# 32_smd.net
KiCad netlist of a schematic drawn in EAGLE
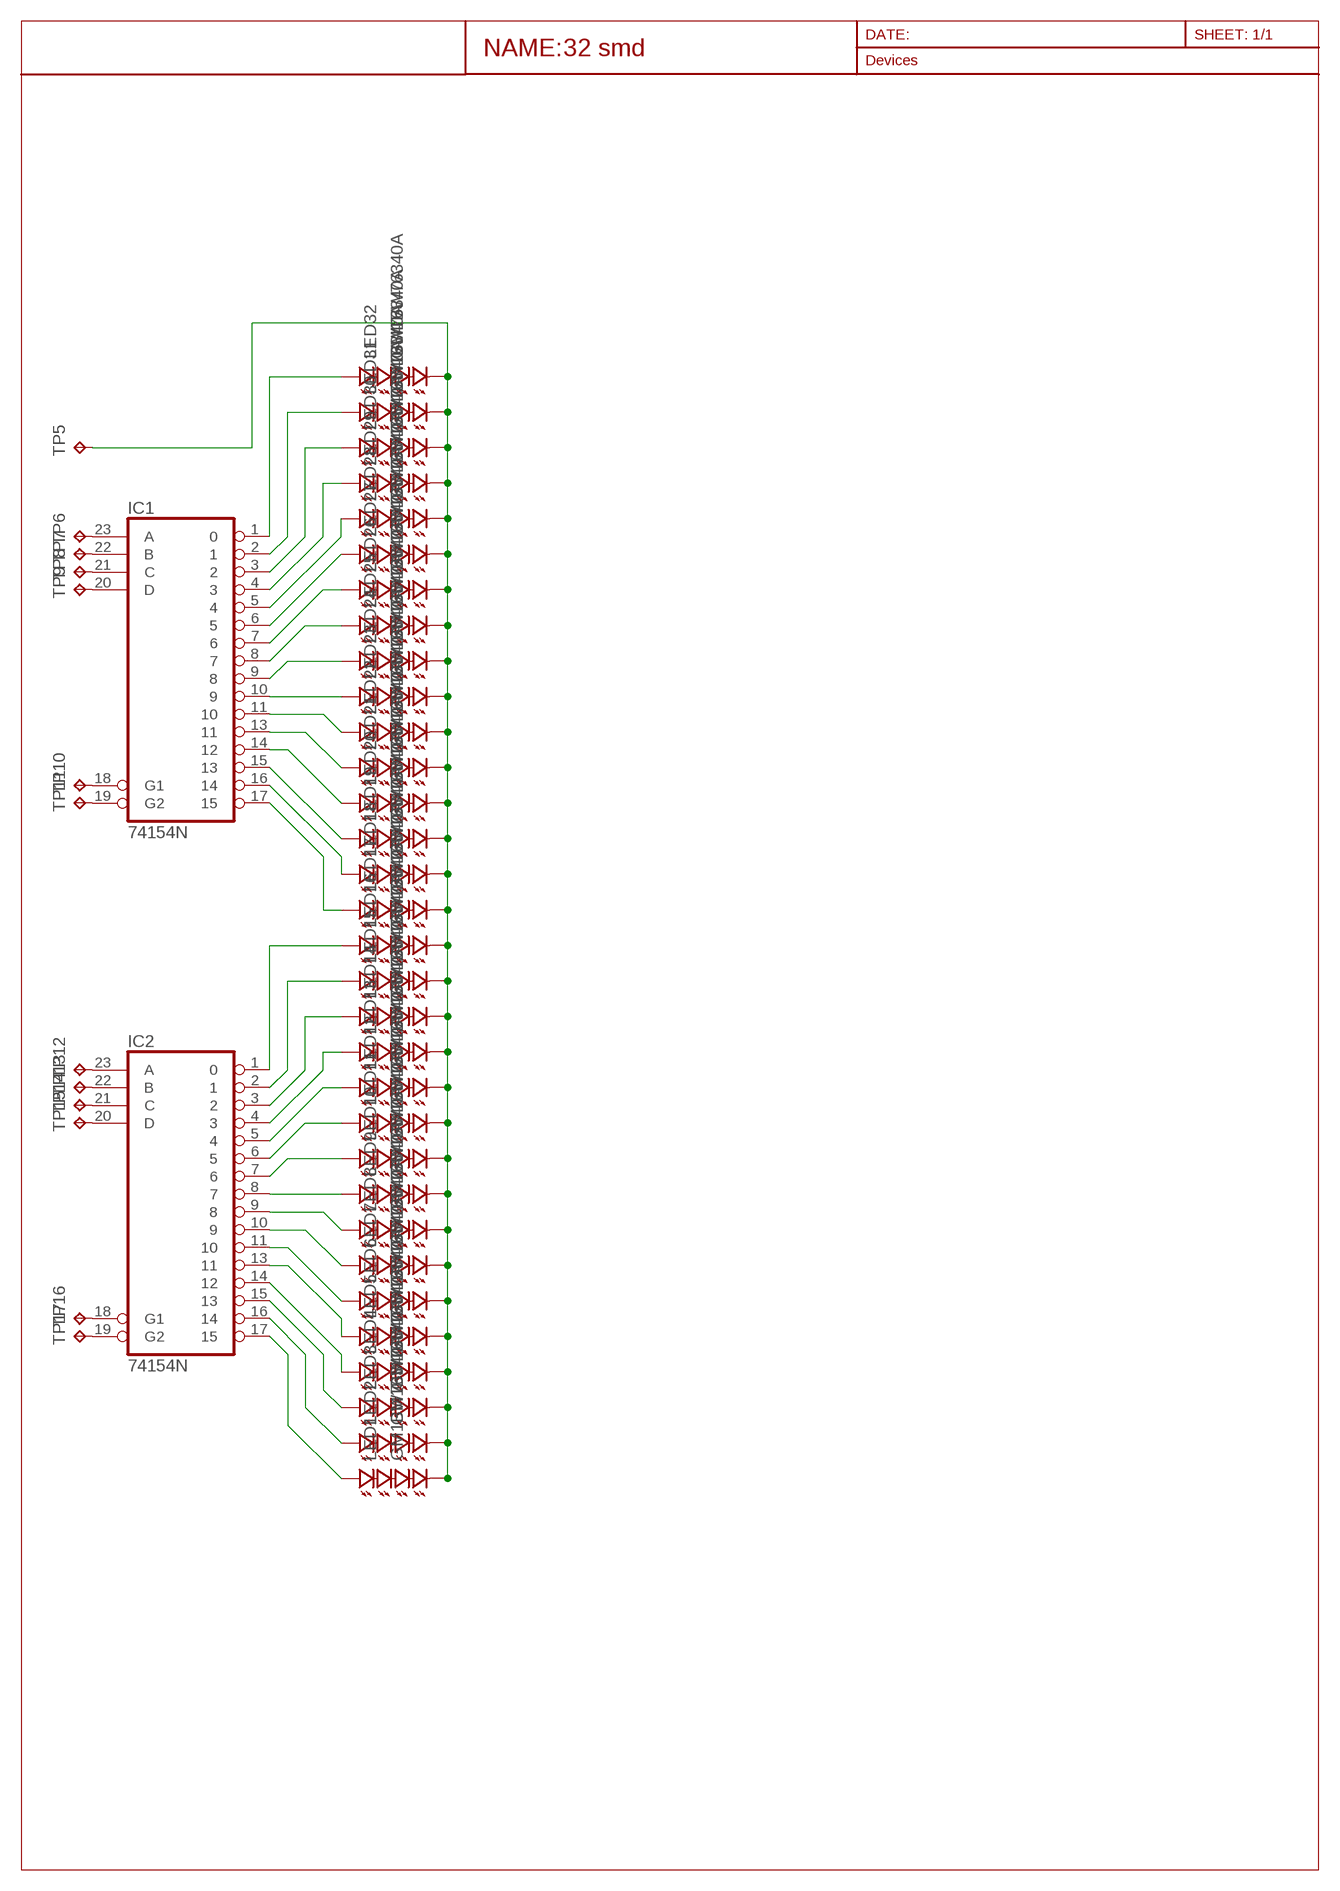
[diagram p0: schematic, sheet 1]

(export (version "E")
  (design (tool "Eeschema 10.0.6"))
  (components
    (comp (ref "IC1")
      (value "74154N")
      (footprint "eagle-import:DIL24-6")
      (libsource (lib "eagle-import") (part "74154N"))
    )
    (comp (ref "IC2")
      (value "74154N")
      (footprint "eagle-import:DIL24-6")
      (libsource (lib "eagle-import") (part "74154N"))
    )
    (comp (ref "LED1")
      (value "GM1BW76340A")
      (footprint "eagle-import:GM1BW78140A")
      (libsource (lib "eagle-import") (part "GM1BW76340A"))
    )
    (comp (ref "LED2")
      (value "GM1BW76340A")
      (footprint "eagle-import:GM1BW78140A")
      (libsource (lib "eagle-import") (part "GM1BW76340A"))
    )
    (comp (ref "LED3")
      (value "GM1BW76340A")
      (footprint "eagle-import:GM1BW78140A")
      (libsource (lib "eagle-import") (part "GM1BW76340A"))
    )
    (comp (ref "LED4")
      (value "GM1BW76340A")
      (footprint "eagle-import:GM1BW78140A")
      (libsource (lib "eagle-import") (part "GM1BW76340A"))
    )
    (comp (ref "LED5")
      (value "GM1BW76340A")
      (footprint "eagle-import:GM1BW78140A")
      (libsource (lib "eagle-import") (part "GM1BW76340A"))
    )
    (comp (ref "LED6")
      (value "GM1BW76340A")
      (footprint "eagle-import:GM1BW78140A")
      (libsource (lib "eagle-import") (part "GM1BW76340A"))
    )
    (comp (ref "LED7")
      (value "GM1BW76340A")
      (footprint "eagle-import:GM1BW78140A")
      (libsource (lib "eagle-import") (part "GM1BW76340A"))
    )
    (comp (ref "LED8")
      (value "GM1BW76340A")
      (footprint "eagle-import:GM1BW78140A")
      (libsource (lib "eagle-import") (part "GM1BW76340A"))
    )
    (comp (ref "LED9")
      (value "GM1BW76340A")
      (footprint "eagle-import:GM1BW78140A")
      (libsource (lib "eagle-import") (part "GM1BW76340A"))
    )
    (comp (ref "LED10")
      (value "GM1BW76340A")
      (footprint "eagle-import:GM1BW78140A")
      (libsource (lib "eagle-import") (part "GM1BW76340A"))
    )
    (comp (ref "LED11")
      (value "GM1BW76340A")
      (footprint "eagle-import:GM1BW78140A")
      (libsource (lib "eagle-import") (part "GM1BW76340A"))
    )
    (comp (ref "LED12")
      (value "GM1BW76340A")
      (footprint "eagle-import:GM1BW78140A")
      (libsource (lib "eagle-import") (part "GM1BW76340A"))
    )
    (comp (ref "LED13")
      (value "GM1BW76340A")
      (footprint "eagle-import:GM1BW78140A")
      (libsource (lib "eagle-import") (part "GM1BW76340A"))
    )
    (comp (ref "LED14")
      (value "GM1BW76340A")
      (footprint "eagle-import:GM1BW78140A")
      (libsource (lib "eagle-import") (part "GM1BW76340A"))
    )
    (comp (ref "LED15")
      (value "GM1BW76340A")
      (footprint "eagle-import:GM1BW78140A")
      (libsource (lib "eagle-import") (part "GM1BW76340A"))
    )
    (comp (ref "LED16")
      (value "GM1BW76340A")
      (footprint "eagle-import:GM1BW78140A")
      (libsource (lib "eagle-import") (part "GM1BW76340A"))
    )
    (comp (ref "LED17")
      (value "GM1BW76340A")
      (footprint "eagle-import:GM1BW78140A")
      (libsource (lib "eagle-import") (part "GM1BW76340A"))
    )
    (comp (ref "LED18")
      (value "GM1BW76340A")
      (footprint "eagle-import:GM1BW78140A")
      (libsource (lib "eagle-import") (part "GM1BW76340A"))
    )
    (comp (ref "LED19")
      (value "GM1BW76340A")
      (footprint "eagle-import:GM1BW78140A")
      (libsource (lib "eagle-import") (part "GM1BW76340A"))
    )
    (comp (ref "LED20")
      (value "GM1BW76340A")
      (footprint "eagle-import:GM1BW78140A")
      (libsource (lib "eagle-import") (part "GM1BW76340A"))
    )
    (comp (ref "LED21")
      (value "GM1BW76340A")
      (footprint "eagle-import:GM1BW78140A")
      (libsource (lib "eagle-import") (part "GM1BW76340A"))
    )
    (comp (ref "LED22")
      (value "GM1BW76340A")
      (footprint "eagle-import:GM1BW78140A")
      (libsource (lib "eagle-import") (part "GM1BW76340A"))
    )
    (comp (ref "LED23")
      (value "GM1BW76340A")
      (footprint "eagle-import:GM1BW78140A")
      (libsource (lib "eagle-import") (part "GM1BW76340A"))
    )
    (comp (ref "LED24")
      (value "GM1BW76340A")
      (footprint "eagle-import:GM1BW78140A")
      (libsource (lib "eagle-import") (part "GM1BW76340A"))
    )
    (comp (ref "LED25")
      (value "GM1BW76340A")
      (footprint "eagle-import:GM1BW78140A")
      (libsource (lib "eagle-import") (part "GM1BW76340A"))
    )
    (comp (ref "LED26")
      (value "GM1BW76340A")
      (footprint "eagle-import:GM1BW78140A")
      (libsource (lib "eagle-import") (part "GM1BW76340A"))
    )
    (comp (ref "LED27")
      (value "GM1BW76340A")
      (footprint "eagle-import:GM1BW78140A")
      (libsource (lib "eagle-import") (part "GM1BW76340A"))
    )
    (comp (ref "LED28")
      (value "GM1BW76340A")
      (footprint "eagle-import:GM1BW78140A")
      (libsource (lib "eagle-import") (part "GM1BW76340A"))
    )
    (comp (ref "LED29")
      (value "GM1BW76340A")
      (footprint "eagle-import:GM1BW78140A")
      (libsource (lib "eagle-import") (part "GM1BW76340A"))
    )
    (comp (ref "LED30")
      (value "GM1BW76340A")
      (footprint "eagle-import:GM1BW78140A")
      (libsource (lib "eagle-import") (part "GM1BW76340A"))
    )
    (comp (ref "LED31")
      (value "GM1BW76340A")
      (footprint "eagle-import:GM1BW78140A")
      (libsource (lib "eagle-import") (part "GM1BW76340A"))
    )
    (comp (ref "LED32")
      (value "GM1BW76340A")
      (footprint "eagle-import:GM1BW78140A")
      (libsource (lib "eagle-import") (part "GM1BW76340A"))
    )
    (comp (ref "TP5")
      (value "TPPAD1-17Y")
      (footprint "eagle-import:P1-17Y")
      (libsource (lib "eagle-import") (part "TPPAD1-17Y"))
    )
    (comp (ref "TP6")
      (value "TPPAD1-17Y")
      (footprint "eagle-import:P1-17Y")
      (libsource (lib "eagle-import") (part "TPPAD1-17Y"))
    )
    (comp (ref "TP7")
      (value "TPPAD1-17Y")
      (footprint "eagle-import:P1-17Y")
      (libsource (lib "eagle-import") (part "TPPAD1-17Y"))
    )
    (comp (ref "TP8")
      (value "TPPAD1-17Y")
      (footprint "eagle-import:P1-17Y")
      (libsource (lib "eagle-import") (part "TPPAD1-17Y"))
    )
    (comp (ref "TP9")
      (value "TPPAD1-17Y")
      (footprint "eagle-import:P1-17Y")
      (libsource (lib "eagle-import") (part "TPPAD1-17Y"))
    )
    (comp (ref "TP10")
      (value "TPPAD1-17Y")
      (footprint "eagle-import:P1-17Y")
      (libsource (lib "eagle-import") (part "TPPAD1-17Y"))
    )
    (comp (ref "TP11")
      (value "TPPAD1-17Y")
      (footprint "eagle-import:P1-17Y")
      (libsource (lib "eagle-import") (part "TPPAD1-17Y"))
    )
    (comp (ref "TP12")
      (value "TPPAD1-17Y")
      (footprint "eagle-import:P1-17Y")
      (libsource (lib "eagle-import") (part "TPPAD1-17Y"))
    )
    (comp (ref "TP13")
      (value "TPPAD1-17Y")
      (footprint "eagle-import:P1-17Y")
      (libsource (lib "eagle-import") (part "TPPAD1-17Y"))
    )
    (comp (ref "TP14")
      (value "TPPAD1-17Y")
      (footprint "eagle-import:P1-17Y")
      (libsource (lib "eagle-import") (part "TPPAD1-17Y"))
    )
    (comp (ref "TP15")
      (value "TPPAD1-17Y")
      (footprint "eagle-import:P1-17Y")
      (libsource (lib "eagle-import") (part "TPPAD1-17Y"))
    )
    (comp (ref "TP16")
      (value "TPPAD1-17Y")
      (footprint "eagle-import:P1-17Y")
      (libsource (lib "eagle-import") (part "TPPAD1-17Y"))
    )
    (comp (ref "TP17")
      (value "TPPAD1-17Y")
      (footprint "eagle-import:P1-17Y")
      (libsource (lib "eagle-import") (part "TPPAD1-17Y"))
    )
  )
  (nets
    (net (code "1") (name "Net-(IC1A-0)") (class "Default")
      (node (ref "IC1") (pin "1") (pinfunction "0_1") (pintype "output"))
      (node (ref "LED32") (pin "A") (pinfunction "A_A") (pintype "passive"))
    )
    (net (code "2") (name "Net-(IC1A-1)") (class "Default")
      (node (ref "IC1") (pin "2") (pinfunction "1_2") (pintype "output"))
      (node (ref "LED31") (pin "A") (pinfunction "A_A") (pintype "passive"))
    )
    (net (code "3") (name "Net-(IC1A-2)") (class "Default")
      (node (ref "IC1") (pin "3") (pinfunction "2_3") (pintype "output"))
      (node (ref "LED30") (pin "A") (pinfunction "A_A") (pintype "passive"))
    )
    (net (code "4") (name "Net-(IC1A-3)") (class "Default")
      (node (ref "IC1") (pin "4") (pinfunction "3_4") (pintype "output"))
      (node (ref "LED29") (pin "A") (pinfunction "A_A") (pintype "passive"))
    )
    (net (code "5") (name "Net-(IC1A-4)") (class "Default")
      (node (ref "IC1") (pin "5") (pinfunction "4_5") (pintype "output"))
      (node (ref "LED28") (pin "A") (pinfunction "A_A") (pintype "passive"))
    )
    (net (code "6") (name "Net-(IC1A-5)") (class "Default")
      (node (ref "IC1") (pin "6") (pinfunction "5_6") (pintype "output"))
      (node (ref "LED27") (pin "A") (pinfunction "A_A") (pintype "passive"))
    )
    (net (code "7") (name "Net-(IC1A-6)") (class "Default")
      (node (ref "IC1") (pin "7") (pinfunction "6_7") (pintype "output"))
      (node (ref "LED26") (pin "A") (pinfunction "A_A") (pintype "passive"))
    )
    (net (code "8") (name "Net-(IC1A-7)") (class "Default")
      (node (ref "IC1") (pin "8") (pinfunction "7_8") (pintype "output"))
      (node (ref "LED25") (pin "A") (pinfunction "A_A") (pintype "passive"))
    )
    (net (code "9") (name "Net-(IC1A-8)") (class "Default")
      (node (ref "IC1") (pin "9") (pinfunction "8_9") (pintype "output"))
      (node (ref "LED24") (pin "A") (pinfunction "A_A") (pintype "passive"))
    )
    (net (code "10") (name "Net-(IC1A-9)") (class "Default")
      (node (ref "IC1") (pin "10") (pinfunction "9_10") (pintype "output"))
      (node (ref "LED23") (pin "A") (pinfunction "A_A") (pintype "passive"))
    )
    (net (code "11") (name "Net-(IC1A-10)") (class "Default")
      (node (ref "IC1") (pin "11") (pinfunction "10_11") (pintype "output"))
      (node (ref "LED22") (pin "A") (pinfunction "A_A") (pintype "passive"))
    )
    (net (code "12") (name "Net-(IC1A-11)") (class "Default")
      (node (ref "IC1") (pin "13") (pinfunction "11_13") (pintype "output"))
      (node (ref "LED21") (pin "A") (pinfunction "A_A") (pintype "passive"))
    )
    (net (code "13") (name "Net-(IC1A-12)") (class "Default")
      (node (ref "IC1") (pin "14") (pinfunction "12_14") (pintype "output"))
      (node (ref "LED20") (pin "A") (pinfunction "A_A") (pintype "passive"))
    )
    (net (code "14") (name "Net-(IC1A-13)") (class "Default")
      (node (ref "IC1") (pin "15") (pinfunction "13_15") (pintype "output"))
      (node (ref "LED19") (pin "A") (pinfunction "A_A") (pintype "passive"))
    )
    (net (code "15") (name "Net-(IC1A-14)") (class "Default")
      (node (ref "IC1") (pin "16") (pinfunction "14_16") (pintype "output"))
      (node (ref "LED18") (pin "A") (pinfunction "A_A") (pintype "passive"))
    )
    (net (code "16") (name "Net-(IC1A-15)") (class "Default")
      (node (ref "IC1") (pin "17") (pinfunction "15_17") (pintype "output"))
      (node (ref "LED17") (pin "A") (pinfunction "A_A") (pintype "passive"))
    )
    (net (code "17") (name "Net-(IC1A-A)") (class "Default")
      (node (ref "IC1") (pin "23") (pinfunction "A_23") (pintype "input"))
      (node (ref "TP6") (pin "TP") (pinfunction "TP_TP") (pintype "input"))
    )
    (net (code "18") (name "Net-(IC1A-B)") (class "Default")
      (node (ref "IC1") (pin "22") (pinfunction "B_22") (pintype "input"))
      (node (ref "TP7") (pin "TP") (pinfunction "TP_TP") (pintype "input"))
    )
    (net (code "19") (name "Net-(IC1A-C)") (class "Default")
      (node (ref "IC1") (pin "21") (pinfunction "C_21") (pintype "input"))
      (node (ref "TP8") (pin "TP") (pinfunction "TP_TP") (pintype "input"))
    )
    (net (code "20") (name "Net-(IC1A-D)") (class "Default")
      (node (ref "IC1") (pin "20") (pinfunction "D_20") (pintype "input"))
      (node (ref "TP9") (pin "TP") (pinfunction "TP_TP") (pintype "input"))
    )
    (net (code "21") (name "Net-(IC1A-G1)") (class "Default")
      (node (ref "IC1") (pin "18") (pinfunction "G1_18") (pintype "input"))
      (node (ref "TP10") (pin "TP") (pinfunction "TP_TP") (pintype "input"))
    )
    (net (code "22") (name "Net-(IC1A-G2)") (class "Default")
      (node (ref "IC1") (pin "19") (pinfunction "G2_19") (pintype "input"))
      (node (ref "TP11") (pin "TP") (pinfunction "TP_TP") (pintype "input"))
    )
    (net (code "23") (name "Net-(IC2A-0)") (class "Default")
      (node (ref "IC2") (pin "1") (pinfunction "0_1") (pintype "output"))
      (node (ref "LED16") (pin "A") (pinfunction "A_A") (pintype "passive"))
    )
    (net (code "24") (name "Net-(IC2A-1)") (class "Default")
      (node (ref "IC2") (pin "2") (pinfunction "1_2") (pintype "output"))
      (node (ref "LED15") (pin "A") (pinfunction "A_A") (pintype "passive"))
    )
    (net (code "25") (name "Net-(IC2A-2)") (class "Default")
      (node (ref "IC2") (pin "3") (pinfunction "2_3") (pintype "output"))
      (node (ref "LED14") (pin "A") (pinfunction "A_A") (pintype "passive"))
    )
    (net (code "26") (name "Net-(IC2A-3)") (class "Default")
      (node (ref "IC2") (pin "4") (pinfunction "3_4") (pintype "output"))
      (node (ref "LED13") (pin "A") (pinfunction "A_A") (pintype "passive"))
    )
    (net (code "27") (name "Net-(IC2A-4)") (class "Default")
      (node (ref "IC2") (pin "5") (pinfunction "4_5") (pintype "output"))
      (node (ref "LED12") (pin "A") (pinfunction "A_A") (pintype "passive"))
    )
    (net (code "28") (name "Net-(IC2A-5)") (class "Default")
      (node (ref "IC2") (pin "6") (pinfunction "5_6") (pintype "output"))
      (node (ref "LED11") (pin "A") (pinfunction "A_A") (pintype "passive"))
    )
    (net (code "29") (name "Net-(IC2A-6)") (class "Default")
      (node (ref "IC2") (pin "7") (pinfunction "6_7") (pintype "output"))
      (node (ref "LED10") (pin "A") (pinfunction "A_A") (pintype "passive"))
    )
    (net (code "30") (name "Net-(IC2A-7)") (class "Default")
      (node (ref "IC2") (pin "8") (pinfunction "7_8") (pintype "output"))
      (node (ref "LED9") (pin "A") (pinfunction "A_A") (pintype "passive"))
    )
    (net (code "31") (name "Net-(IC2A-8)") (class "Default")
      (node (ref "IC2") (pin "9") (pinfunction "8_9") (pintype "output"))
      (node (ref "LED8") (pin "A") (pinfunction "A_A") (pintype "passive"))
    )
    (net (code "32") (name "Net-(IC2A-9)") (class "Default")
      (node (ref "IC2") (pin "10") (pinfunction "9_10") (pintype "output"))
      (node (ref "LED7") (pin "A") (pinfunction "A_A") (pintype "passive"))
    )
    (net (code "33") (name "Net-(IC2A-10)") (class "Default")
      (node (ref "IC2") (pin "11") (pinfunction "10_11") (pintype "output"))
      (node (ref "LED6") (pin "A") (pinfunction "A_A") (pintype "passive"))
    )
    (net (code "34") (name "Net-(IC2A-11)") (class "Default")
      (node (ref "IC2") (pin "13") (pinfunction "11_13") (pintype "output"))
      (node (ref "LED5") (pin "A") (pinfunction "A_A") (pintype "passive"))
    )
    (net (code "35") (name "Net-(IC2A-12)") (class "Default")
      (node (ref "IC2") (pin "14") (pinfunction "12_14") (pintype "output"))
      (node (ref "LED4") (pin "A") (pinfunction "A_A") (pintype "passive"))
    )
    (net (code "36") (name "Net-(IC2A-13)") (class "Default")
      (node (ref "IC2") (pin "15") (pinfunction "13_15") (pintype "output"))
      (node (ref "LED3") (pin "A") (pinfunction "A_A") (pintype "passive"))
    )
    (net (code "37") (name "Net-(IC2A-14)") (class "Default")
      (node (ref "IC2") (pin "16") (pinfunction "14_16") (pintype "output"))
      (node (ref "LED2") (pin "A") (pinfunction "A_A") (pintype "passive"))
    )
    (net (code "38") (name "Net-(IC2A-15)") (class "Default")
      (node (ref "IC2") (pin "17") (pinfunction "15_17") (pintype "output"))
      (node (ref "LED1") (pin "A") (pinfunction "A_A") (pintype "passive"))
    )
    (net (code "39") (name "Net-(IC2A-A)") (class "Default")
      (node (ref "IC2") (pin "23") (pinfunction "A_23") (pintype "input"))
      (node (ref "TP12") (pin "TP") (pinfunction "TP_TP") (pintype "input"))
    )
    (net (code "40") (name "Net-(IC2A-B)") (class "Default")
      (node (ref "IC2") (pin "22") (pinfunction "B_22") (pintype "input"))
      (node (ref "TP13") (pin "TP") (pinfunction "TP_TP") (pintype "input"))
    )
    (net (code "41") (name "Net-(IC2A-C)") (class "Default")
      (node (ref "IC2") (pin "21") (pinfunction "C_21") (pintype "input"))
      (node (ref "TP14") (pin "TP") (pinfunction "TP_TP") (pintype "input"))
    )
    (net (code "42") (name "Net-(IC2A-D)") (class "Default")
      (node (ref "IC2") (pin "20") (pinfunction "D_20") (pintype "input"))
      (node (ref "TP15") (pin "TP") (pinfunction "TP_TP") (pintype "input"))
    )
    (net (code "43") (name "Net-(IC2A-G1)") (class "Default")
      (node (ref "IC2") (pin "18") (pinfunction "G1_18") (pintype "input"))
      (node (ref "TP16") (pin "TP") (pinfunction "TP_TP") (pintype "input"))
    )
    (net (code "44") (name "Net-(IC2A-G2)") (class "Default")
      (node (ref "IC2") (pin "19") (pinfunction "G2_19") (pintype "input"))
      (node (ref "TP17") (pin "TP") (pinfunction "TP_TP") (pintype "input"))
    )
    (net (code "45") (name "Net-(LED1-PadC)") (class "Default")
      (node (ref "LED1") (pin "C") (pinfunction "C_C") (pintype "passive"))
      (node (ref "LED10") (pin "C") (pinfunction "C_C") (pintype "passive"))
      (node (ref "LED11") (pin "C") (pinfunction "C_C") (pintype "passive"))
      (node (ref "LED12") (pin "C") (pinfunction "C_C") (pintype "passive"))
      (node (ref "LED13") (pin "C") (pinfunction "C_C") (pintype "passive"))
      (node (ref "LED14") (pin "C") (pinfunction "C_C") (pintype "passive"))
      (node (ref "LED15") (pin "C") (pinfunction "C_C") (pintype "passive"))
      (node (ref "LED16") (pin "C") (pinfunction "C_C") (pintype "passive"))
      (node (ref "LED17") (pin "C") (pinfunction "C_C") (pintype "passive"))
      (node (ref "LED18") (pin "C") (pinfunction "C_C") (pintype "passive"))
      (node (ref "LED19") (pin "C") (pinfunction "C_C") (pintype "passive"))
      (node (ref "LED2") (pin "C") (pinfunction "C_C") (pintype "passive"))
      (node (ref "LED20") (pin "C") (pinfunction "C_C") (pintype "passive"))
      (node (ref "LED21") (pin "C") (pinfunction "C_C") (pintype "passive"))
      (node (ref "LED22") (pin "C") (pinfunction "C_C") (pintype "passive"))
      (node (ref "LED23") (pin "C") (pinfunction "C_C") (pintype "passive"))
      (node (ref "LED24") (pin "C") (pinfunction "C_C") (pintype "passive"))
      (node (ref "LED25") (pin "C") (pinfunction "C_C") (pintype "passive"))
      (node (ref "LED26") (pin "C") (pinfunction "C_C") (pintype "passive"))
      (node (ref "LED27") (pin "C") (pinfunction "C_C") (pintype "passive"))
      (node (ref "LED28") (pin "C") (pinfunction "C_C") (pintype "passive"))
      (node (ref "LED29") (pin "C") (pinfunction "C_C") (pintype "passive"))
      (node (ref "LED3") (pin "C") (pinfunction "C_C") (pintype "passive"))
      (node (ref "LED30") (pin "C") (pinfunction "C_C") (pintype "passive"))
      (node (ref "LED31") (pin "C") (pinfunction "C_C") (pintype "passive"))
      (node (ref "LED32") (pin "C") (pinfunction "C_C") (pintype "passive"))
      (node (ref "LED4") (pin "C") (pinfunction "C_C") (pintype "passive"))
      (node (ref "LED5") (pin "C") (pinfunction "C_C") (pintype "passive"))
      (node (ref "LED6") (pin "C") (pinfunction "C_C") (pintype "passive"))
      (node (ref "LED7") (pin "C") (pinfunction "C_C") (pintype "passive"))
      (node (ref "LED8") (pin "C") (pinfunction "C_C") (pintype "passive"))
      (node (ref "LED9") (pin "C") (pinfunction "C_C") (pintype "passive"))
      (node (ref "TP5") (pin "TP") (pinfunction "TP_TP") (pintype "input"))
    )
  )
)
